# Loads.net
KiCad netlist of a schematic drawn in Altium Designer
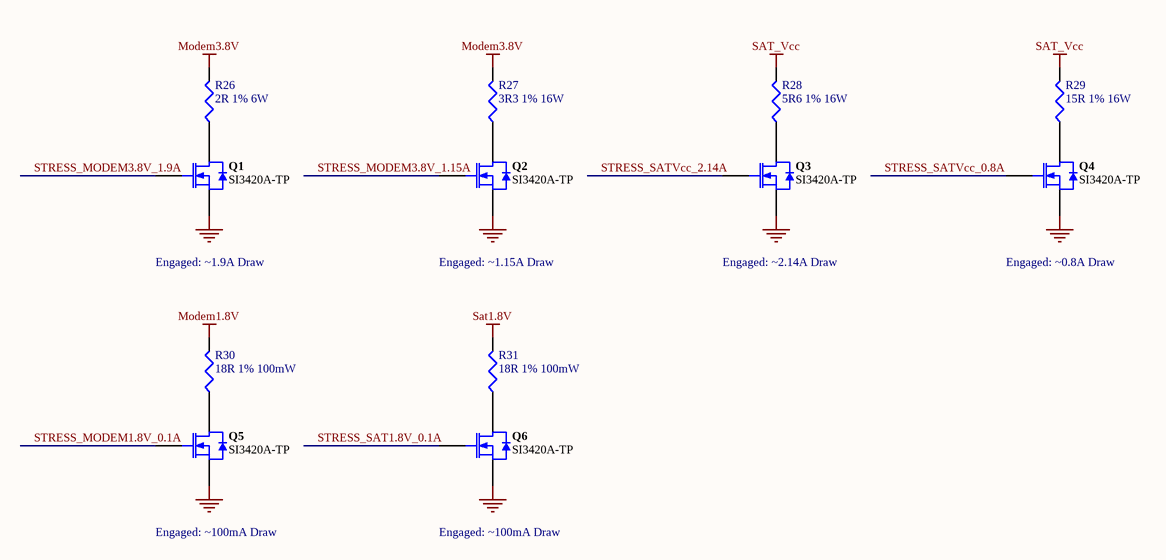
[diagram p0: Loads.SchDoc]

(export (version "E")
  (design (tool "Eeschema 10.0.6"))
  (components
    (comp (ref "Q1")
      (value "SI3420A-TP")
      (footprint "INF-PG-SOT23_L")
      (description "MOSFET N-CH 20V 6A SOT-23")
      (fields (field (name "MANUFACTURER") "Micro Commercial Co"))
      (libsource (lib "Infineon Power MOSFET") (part "2N7002"))
    )
    (comp (ref "Q2")
      (value "SI3420A-TP")
      (footprint "INF-PG-SOT23_L")
      (description "MOSFET N-CH 20V 6A SOT-23")
      (fields (field (name "MANUFACTURER") "Micro Commercial Co"))
      (libsource (lib "Infineon Power MOSFET") (part "2N7002"))
    )
    (comp (ref "Q3")
      (value "SI3420A-TP")
      (footprint "INF-PG-SOT23_L")
      (description "MOSFET N-CH 20V 6A SOT-23")
      (fields (field (name "MANUFACTURER") "Micro Commercial Co"))
      (libsource (lib "Infineon Power MOSFET") (part "2N7002"))
    )
    (comp (ref "Q4")
      (value "SI3420A-TP")
      (footprint "INF-PG-SOT23_L")
      (description "MOSFET N-CH 20V 6A SOT-23")
      (fields (field (name "MANUFACTURER") "Micro Commercial Co"))
      (libsource (lib "Infineon Power MOSFET") (part "2N7002"))
    )
    (comp (ref "Q5")
      (value "SI3420A-TP")
      (footprint "INF-PG-SOT23_L")
      (description "MOSFET N-CH 20V 6A SOT-23")
      (fields (field (name "MANUFACTURER") "Micro Commercial Co"))
      (libsource (lib "Infineon Power MOSFET") (part "2N7002"))
    )
    (comp (ref "Q6")
      (value "SI3420A-TP")
      (footprint "INF-PG-SOT23_L")
      (description "MOSFET N-CH 20V 6A SOT-23")
      (fields (field (name "MANUFACTURER") "Micro Commercial Co"))
      (libsource (lib "Infineon Power MOSFET") (part "2N7002"))
    )
    (comp (ref "R26")
      (value "2R 1% 6W")
      (footprint "RESC6432AL")
      (description "RES SMD 2 OHM 1% 6W 2512")
      (fields
        (field (name "MANUFACTURER") "Vishay Thin Film")
        (field (name "MANUFACTURER PART NUMBER") "PCNM2512K2R00FST5")
      )
      (libsource (lib "Miscellaneous Devices") (part "Res3"))
    )
    (comp (ref "R27")
      (value "3R3 1% 16W")
      (footprint "RESC6432AL")
      (description "RES SMD 3.3 OHM 1% 16W 2512")
      (fields
        (field (name "MANUFACTURER") "Susumu")
        (field (name "MANUFACTURER PART NUMBER") "CPA2512Q3R30FS-T10")
      )
      (libsource (lib "Miscellaneous Devices") (part "Res3"))
    )
    (comp (ref "R28")
      (value "5R6 1% 16W")
      (footprint "RESC6432AL")
      (description "RES SMD 5.6 OHM 1% 16W 2512")
      (fields
        (field (name "MANUFACTURER") "Susumu")
        (field (name "MANUFACTURER PART NUMBER") "CPA2512Q5R60FS-T10")
      )
      (libsource (lib "Miscellaneous Devices") (part "Res3"))
    )
    (comp (ref "R29")
      (value "15R 1% 16W")
      (footprint "RESC6432AL")
      (description "RES SMD 15 OHM 1% 16W 2512")
      (fields
        (field (name "MANUFACTURER") "Susumu")
        (field (name "MANUFACTURER PART NUMBER") "CPA2512Q15R0FS-T10")
      )
      (libsource (lib "Miscellaneous Devices") (part "Res3"))
    )
    (comp (ref "R30")
      (value "18R 1% 100mW")
      (footprint "J1-0603")
      (description "Resistor")
      (libsource (lib "Miscellaneous Devices") (part "Res3"))
    )
    (comp (ref "R31")
      (value "18R 1% 100mW")
      (footprint "J1-0603")
      (description "Resistor")
      (libsource (lib "Miscellaneous Devices") (part "Res3"))
    )
  )
  (nets
    (net (code "1") (name "/STRESS_MODEM1.8V_0.1A") (class "Default")
      (node (ref "Q5") (pin "1") (pinfunction "GATE_1") (pintype "passive"))
    )
    (net (code "2") (name "/STRESS_MODEM3.8V_1.9A") (class "Default")
      (node (ref "Q1") (pin "1") (pinfunction "GATE_1") (pintype "passive"))
    )
    (net (code "3") (name "/STRESS_MODEM3.8V_1.15A") (class "Default")
      (node (ref "Q2") (pin "1") (pinfunction "GATE_1") (pintype "passive"))
    )
    (net (code "4") (name "/STRESS_SAT1.8V_0.1A") (class "Default")
      (node (ref "Q6") (pin "1") (pinfunction "GATE_1") (pintype "passive"))
    )
    (net (code "5") (name "/STRESS_SATVcc_0.8A") (class "Default")
      (node (ref "Q4") (pin "1") (pinfunction "GATE_1") (pintype "passive"))
    )
    (net (code "6") (name "/STRESS_SATVcc_2.14A") (class "Default")
      (node (ref "Q3") (pin "1") (pinfunction "GATE_1") (pintype "passive"))
    )
    (net (code "7") (name "GND") (class "Default")
      (node (ref "Q1") (pin "2") (pinfunction "SOURCE_2") (pintype "passive"))
      (node (ref "Q2") (pin "2") (pinfunction "SOURCE_2") (pintype "passive"))
      (node (ref "Q3") (pin "2") (pinfunction "SOURCE_2") (pintype "passive"))
      (node (ref "Q4") (pin "2") (pinfunction "SOURCE_2") (pintype "passive"))
      (node (ref "Q5") (pin "2") (pinfunction "SOURCE_2") (pintype "passive"))
      (node (ref "Q6") (pin "2") (pinfunction "SOURCE_2") (pintype "passive"))
    )
    (net (code "8") (name "Modem1.8V") (class "Default")
      (node (ref "R30") (pin "2") (pinfunction "2_2") (pintype "passive"))
    )
    (net (code "9") (name "Modem3.8V") (class "Default")
      (node (ref "R26") (pin "2") (pinfunction "2_2") (pintype "passive"))
      (node (ref "R27") (pin "2") (pinfunction "2_2") (pintype "passive"))
    )
    (net (code "10") (name "Net-(Q1-DRAIN)") (class "Default")
      (node (ref "Q1") (pin "3") (pinfunction "DRAIN_3") (pintype "passive"))
      (node (ref "R26") (pin "1") (pinfunction "1_1") (pintype "passive"))
    )
    (net (code "11") (name "Net-(Q2-DRAIN)") (class "Default")
      (node (ref "Q2") (pin "3") (pinfunction "DRAIN_3") (pintype "passive"))
      (node (ref "R27") (pin "1") (pinfunction "1_1") (pintype "passive"))
    )
    (net (code "12") (name "Net-(Q3-DRAIN)") (class "Default")
      (node (ref "Q3") (pin "3") (pinfunction "DRAIN_3") (pintype "passive"))
      (node (ref "R28") (pin "1") (pinfunction "1_1") (pintype "passive"))
    )
    (net (code "13") (name "Net-(Q4-DRAIN)") (class "Default")
      (node (ref "Q4") (pin "3") (pinfunction "DRAIN_3") (pintype "passive"))
      (node (ref "R29") (pin "1") (pinfunction "1_1") (pintype "passive"))
    )
    (net (code "14") (name "Net-(Q5-DRAIN)") (class "Default")
      (node (ref "Q5") (pin "3") (pinfunction "DRAIN_3") (pintype "passive"))
      (node (ref "R30") (pin "1") (pinfunction "1_1") (pintype "passive"))
    )
    (net (code "15") (name "Net-(Q6-DRAIN)") (class "Default")
      (node (ref "Q6") (pin "3") (pinfunction "DRAIN_3") (pintype "passive"))
      (node (ref "R31") (pin "1") (pinfunction "1_1") (pintype "passive"))
    )
    (net (code "16") (name "SAT_Vcc") (class "Default")
      (node (ref "R28") (pin "2") (pinfunction "2_2") (pintype "passive"))
      (node (ref "R29") (pin "2") (pinfunction "2_2") (pintype "passive"))
    )
    (net (code "17") (name "Sat1.8V") (class "Default")
      (node (ref "R31") (pin "2") (pinfunction "2_2") (pintype "passive"))
    )
  )
)
